# SensorBoardv2.net
KiCad netlist of a schematic drawn in Altium Designer
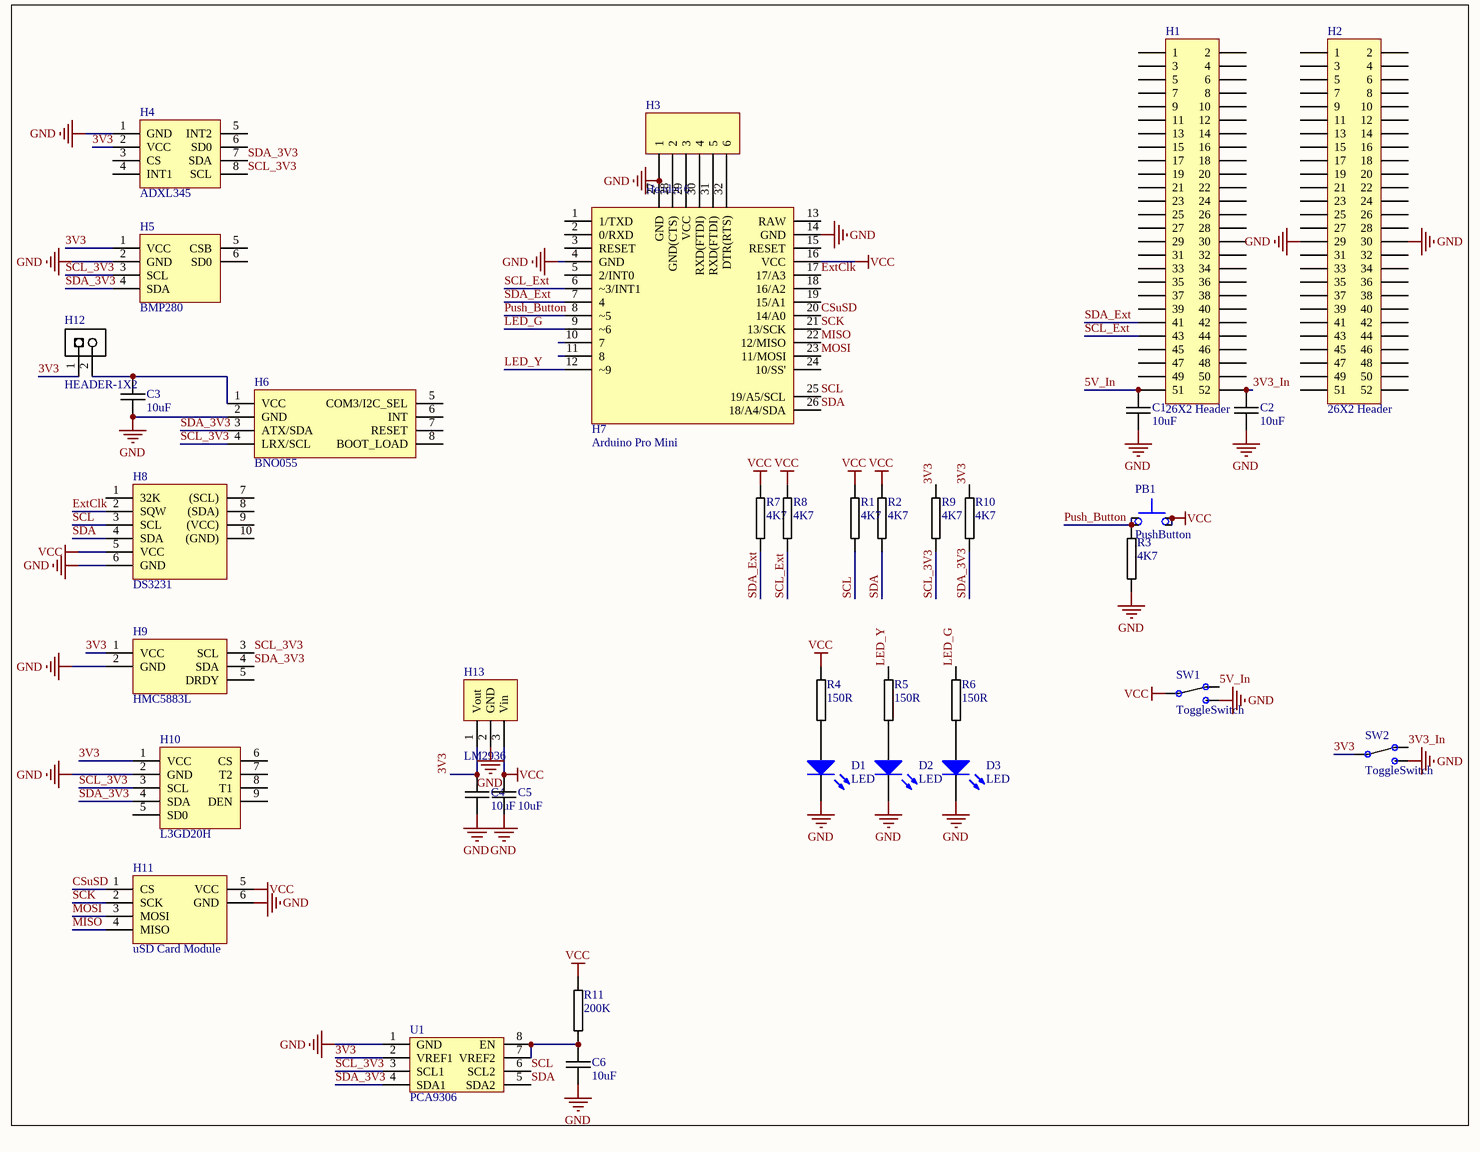
[diagram p0: SensorBoardv2.SchDoc]

(export (version "E")
  (design (tool "Eeschema 10.0.6"))
  (components
    (comp (ref "C1")
      (value "10uF")
      (footprint "0805C-TBD")
      (description "CAPACITOR 0805 CERAMIC")
      (libsource (lib "vh_altium_library") (part "0805C-100nF-25V-X7R-MUR"))
    )
    (comp (ref "C2")
      (value "10uF")
      (footprint "0805C-TBD")
      (description "CAPACITOR 0805 CERAMIC")
      (libsource (lib "vh_altium_library") (part "0805C-100nF-25V-X7R-MUR"))
    )
    (comp (ref "C3")
      (value "10uF")
      (footprint "0805C-GENERIC")
      (description "CAPACITOR 0805 CERAMIC")
      (fields
        (field (name "MANUFACTURER PART NUMBER") "C2012X5R1C106M")
        (field (name "MANUFACTURER") "TDK Corporation")
      )
      (libsource (lib "vh_altium_library") (part "0805C-10UF-16V-X5R-TDK"))
    )
    (comp (ref "C4")
      (value "10uF")
      (footprint "0805C-GENERIC")
      (description "CAPACITOR 0805 CERAMIC")
      (fields
        (field (name "MANUFACTURER PART NUMBER") "C2012X5R1C106M")
        (field (name "MANUFACTURER") "TDK Corporation")
      )
      (libsource (lib "vh_altium_library") (part "0805C-10UF-16V-X5R-TDK"))
    )
    (comp (ref "C5")
      (value "10uF")
      (footprint "0805C-GENERIC")
      (description "CAPACITOR 0805 CERAMIC")
      (fields
        (field (name "MANUFACTURER PART NUMBER") "C2012X5R1C106M")
        (field (name "MANUFACTURER") "TDK Corporation")
      )
      (libsource (lib "vh_altium_library") (part "0805C-10UF-16V-X5R-TDK"))
    )
    (comp (ref "C6")
      (value "10uF")
      (footprint "0805C-GENERIC")
      (description "CAPACITOR 0805 CERAMIC")
      (fields
        (field (name "MANUFACTURER PART NUMBER") "C2012X5R1C106M")
        (field (name "MANUFACTURER") "TDK Corporation")
      )
      (libsource (lib "vh_altium_library") (part "0805C-10UF-16V-X5R-TDK"))
    )
    (comp (ref "D1")
      (value "LED")
      (footprint "LED")
      (description "Small LED")
      (libsource (lib "Components") (part "LED"))
    )
    (comp (ref "D2")
      (value "LED")
      (footprint "LED")
      (description "Small LED")
      (libsource (lib "Components") (part "LED"))
    )
    (comp (ref "D3")
      (value "LED")
      (footprint "LED")
      (description "Small LED")
      (libsource (lib "Components") (part "LED"))
    )
    (comp (ref "H1")
      (value "26X2 Header")
      (footprint "26X2 Header")
      (libsource (lib "CustomParts") (part "26X2 Header"))
    )
    (comp (ref "H2")
      (value "26X2 Header")
      (footprint "26X2 Header")
      (libsource (lib "CustomParts") (part "26X2 Header"))
    )
    (comp (ref "H3")
      (value "Header 6")
      (footprint "HDR1X6")
      (description "Header, 6-Pin")
      (fields (field (name "PUBLISHER") "Altium Limited"))
      (libsource (lib "Miscellaneous Connectors") (part "Header 6"))
    )
    (comp (ref "H4")
      (value "ADXL345")
      (footprint "ADXL345")
      (description "Accelerometer")
      (libsource (lib "Components") (part "ADXL345"))
    )
    (comp (ref "H5")
      (value "BMP280")
      (footprint "BMP280")
      (description "Temp + Pa Sensor")
      (libsource (lib "Components") (part "BMP280"))
    )
    (comp (ref "H6")
      (value "BNO055")
      (footprint "BNO055")
      (description "Accel+Gyro+Mag")
      (libsource (lib "Components") (part "BNO055"))
    )
    (comp (ref "H7")
      (value "Arduino Pro Mini")
      (footprint "Arduino Pro Mini")
      (libsource (lib "Components") (part "Arduino Pro Mini"))
    )
    (comp (ref "H8")
      (value "DS3231")
      (footprint "RTC")
      (description "RTC")
      (libsource (lib "Components") (part "DS3231"))
    )
    (comp (ref "H9")
      (value "HMC5883L")
      (footprint "HMC5883L")
      (description "Magnetometer")
      (libsource (lib "Components") (part "HMC5883L"))
    )
    (comp (ref "H10")
      (value "L3GD20H")
      (footprint "L3GD20H")
      (description "Gyroscope")
      (libsource (lib "Components") (part "L3GD20H"))
    )
    (comp (ref "H11")
      (value "uSD Card Module")
      (footprint "uSD Card Module")
      (libsource (lib "Components") (part "uSD Card Module"))
    )
    (comp (ref "H12")
      (value "HEADER-1X2")
      (footprint "HEADER-1X2")
      (libsource (lib "vh_altium_library") (part "HEADER-1X2"))
    )
    (comp (ref "H13")
      (value "LM2936")
      (footprint "LM2936")
      (description "3V3 Voltage Regulator")
      (libsource (lib "Components") (part "LM2936"))
    )
    (comp (ref "PB1")
      (value "PushButton")
      (footprint "PushButton")
      (libsource (lib "SBv1Components") (part "PushButton"))
    )
    (comp (ref "R1")
      (value "4K7")
      (footprint "0805R-4K7")
      (description "RESISTOR 0805 1/4 WATT THIN FILM")
      (libsource (lib "vh_altium_library") (part "0805R-4K7"))
    )
    (comp (ref "R2")
      (value "4K7")
      (footprint "0805R-4K7")
      (description "RESISTOR 0805 1/4 WATT THIN FILM")
      (libsource (lib "vh_altium_library") (part "0805R-4K7"))
    )
    (comp (ref "R3")
      (value "4K7")
      (footprint "0805R-4K7")
      (description "RESISTOR 0805 1/4 WATT THIN FILM")
      (libsource (lib "vh_altium_library") (part "0805R-4K7"))
    )
    (comp (ref "R4")
      (value "150R")
      (footprint "0805R-150")
      (description "RESISTOR 0805 1/4 WATT THIN FILM")
      (libsource (lib "vh_altium_library") (part "0805R-150"))
    )
    (comp (ref "R5")
      (value "150R")
      (footprint "0805R-150")
      (description "RESISTOR 0805 1/4 WATT THIN FILM")
      (libsource (lib "vh_altium_library") (part "0805R-150"))
    )
    (comp (ref "R6")
      (value "150R")
      (footprint "0805R-150")
      (description "RESISTOR 0805 1/4 WATT THIN FILM")
      (libsource (lib "vh_altium_library") (part "0805R-150"))
    )
    (comp (ref "R7")
      (value "4K7")
      (footprint "0805R-4K7")
      (description "RESISTOR 0805 1/4 WATT THIN FILM")
      (libsource (lib "vh_altium_library") (part "0805R-4K7"))
    )
    (comp (ref "R8")
      (value "4K7")
      (footprint "0805R-4K7")
      (description "RESISTOR 0805 1/4 WATT THIN FILM")
      (libsource (lib "vh_altium_library") (part "0805R-4K7"))
    )
    (comp (ref "R9")
      (value "4K7")
      (footprint "0805R-4K7")
      (description "RESISTOR 0805 1/4 WATT THIN FILM")
      (libsource (lib "vh_altium_library") (part "0805R-4K7"))
    )
    (comp (ref "R10")
      (value "4K7")
      (footprint "0805R-4K7")
      (description "RESISTOR 0805 1/4 WATT THIN FILM")
      (libsource (lib "vh_altium_library") (part "0805R-4K7"))
    )
    (comp (ref "R11")
      (value "200K")
      (footprint "0805R-4K7")
      (description "RESISTOR 0805 1/4 WATT THIN FILM")
      (libsource (lib "vh_altium_library") (part "0805R-4K7"))
    )
    (comp (ref "SW1")
      (value "ToggleSwitch")
      (footprint "SWITCHFOOTPRINT")
      (libsource (lib "SBv1Components") (part "ToggleSwitch"))
    )
    (comp (ref "SW2")
      (value "ToggleSwitch")
      (footprint "SWITCHFOOTPRINT")
      (libsource (lib "SBv1Components") (part "ToggleSwitch"))
    )
    (comp (ref "U1")
      (value "PCA9306")
      (footprint "PCA9306")
      (description "Dual Bidirectional I2C Voltage Level Translator")
      (libsource (lib "Components") (part "PCA9306"))
    )
  )
  (nets
    (net (code "1") (name "/3V3") (class "Default")
      (node (ref "C4") (pin "2") (pintype "passive"))
      (node (ref "H10") (pin "1") (pinfunction "VCC_1") (pintype "passive"))
      (node (ref "H12") (pin "1") (pintype "passive"))
      (node (ref "H13") (pin "1") (pinfunction "Vout_1") (pintype "passive"))
      (node (ref "H4") (pin "2") (pinfunction "VCC_2") (pintype "passive"))
      (node (ref "H5") (pin "1") (pinfunction "VCC_1") (pintype "passive"))
      (node (ref "H9") (pin "1") (pinfunction "VCC_1") (pintype "passive"))
      (node (ref "R10") (pin "1") (pintype "passive"))
      (node (ref "R9") (pin "1") (pintype "passive"))
      (node (ref "SW2") (pin "23") (pinfunction "23_23") (pintype "passive"))
      (node (ref "U1") (pin "2") (pinfunction "VREF1_2") (pintype "passive"))
    )
    (net (code "2") (name "/3V3_In") (class "Default")
      (node (ref "C2") (pin "1") (pintype "passive"))
      (node (ref "H1") (pin "52") (pinfunction "52_52") (pintype "passive"))
      (node (ref "SW2") (pin "24") (pinfunction "24_24") (pintype "passive"))
    )
    (net (code "3") (name "/5V_In") (class "Default")
      (node (ref "C1") (pin "1") (pintype "passive"))
      (node (ref "H1") (pin "51") (pinfunction "51_51") (pintype "passive"))
      (node (ref "SW1") (pin "24") (pinfunction "24_24") (pintype "passive"))
    )
    (net (code "4") (name "/CSuSD") (class "Default")
      (node (ref "H11") (pin "1") (pinfunction "CS_1") (pintype "passive"))
      (node (ref "H7") (pin "20") (pinfunction "14/A0_20") (pintype "passive"))
    )
    (net (code "5") (name "/ExtClk") (class "Default")
      (node (ref "H7") (pin "17") (pinfunction "17/A3_17") (pintype "passive"))
      (node (ref "H8") (pin "2") (pinfunction "SQW_2") (pintype "passive"))
    )
    (net (code "6") (name "/LED_G") (class "Default")
      (node (ref "H7") (pin "9") (pinfunction "~6_9") (pintype "passive"))
      (node (ref "R6") (pin "1") (pintype "passive"))
    )
    (net (code "7") (name "/LED_Y") (class "Default")
      (node (ref "H7") (pin "12") (pinfunction "~9_12") (pintype "passive"))
      (node (ref "R5") (pin "1") (pintype "passive"))
    )
    (net (code "8") (name "/MISO") (class "Default")
      (node (ref "H11") (pin "4") (pinfunction "MISO_4") (pintype "passive"))
      (node (ref "H7") (pin "22") (pinfunction "12/MISO_22") (pintype "passive"))
    )
    (net (code "9") (name "/MOSI") (class "Default")
      (node (ref "H11") (pin "3") (pinfunction "MOSI_3") (pintype "passive"))
      (node (ref "H7") (pin "23") (pinfunction "11/MOSI_23") (pintype "passive"))
    )
    (net (code "10") (name "/Push_Button") (class "Default")
      (node (ref "H7") (pin "8") (pinfunction "~5_8") (pintype "passive"))
      (node (ref "PB1") (pin "26") (pinfunction "26_26") (pintype "passive"))
      (node (ref "PB1") (pin "28") (pinfunction "28_28") (pintype "passive"))
      (node (ref "R3") (pin "1") (pintype "passive"))
    )
    (net (code "11") (name "/SCK") (class "Default")
      (node (ref "H11") (pin "2") (pinfunction "SCK_2") (pintype "passive"))
      (node (ref "H7") (pin "21") (pinfunction "13/SCK_21") (pintype "passive"))
    )
    (net (code "12") (name "/SCL") (class "Default")
      (node (ref "H7") (pin "25") (pinfunction "19/A5/SCL_25") (pintype "passive"))
      (node (ref "H8") (pin "3") (pinfunction "SCL_3") (pintype "passive"))
      (node (ref "R1") (pin "2") (pintype "passive"))
      (node (ref "U1") (pin "6") (pinfunction "SCL2_6") (pintype "passive"))
    )
    (net (code "13") (name "/SCL_3V3") (class "Default")
      (node (ref "H10") (pin "3") (pinfunction "SCL_3") (pintype "passive"))
      (node (ref "H4") (pin "8") (pinfunction "SCL_8") (pintype "passive"))
      (node (ref "H5") (pin "3") (pinfunction "SCL_3") (pintype "passive"))
      (node (ref "H6") (pin "4") (pinfunction "LRX/SCL_4") (pintype "passive"))
      (node (ref "H9") (pin "3") (pinfunction "SCL_3") (pintype "passive"))
      (node (ref "R9") (pin "2") (pintype "passive"))
      (node (ref "U1") (pin "3") (pinfunction "SCL1_3") (pintype "passive"))
    )
    (net (code "14") (name "/SCL_Ext") (class "Default")
      (node (ref "H1") (pin "43") (pinfunction "43_43") (pintype "passive"))
      (node (ref "H7") (pin "6") (pinfunction "~3/INT1_6") (pintype "passive"))
      (node (ref "R8") (pin "2") (pintype "passive"))
    )
    (net (code "15") (name "/SDA") (class "Default")
      (node (ref "H7") (pin "26") (pinfunction "18/A4/SDA_26") (pintype "passive"))
      (node (ref "H8") (pin "4") (pinfunction "SDA_4") (pintype "passive"))
      (node (ref "R2") (pin "2") (pintype "passive"))
      (node (ref "U1") (pin "5") (pinfunction "SDA2_5") (pintype "passive"))
    )
    (net (code "16") (name "/SDA_3V3") (class "Default")
      (node (ref "H10") (pin "4") (pinfunction "SDA_4") (pintype "passive"))
      (node (ref "H4") (pin "7") (pinfunction "SDA_7") (pintype "passive"))
      (node (ref "H5") (pin "4") (pinfunction "SDA_4") (pintype "passive"))
      (node (ref "H6") (pin "3") (pinfunction "ATX/SDA_3") (pintype "passive"))
      (node (ref "H9") (pin "4") (pinfunction "SDA_4") (pintype "passive"))
      (node (ref "R10") (pin "2") (pintype "passive"))
      (node (ref "U1") (pin "4") (pinfunction "SDA1_4") (pintype "passive"))
    )
    (net (code "17") (name "/SDA_Ext") (class "Default")
      (node (ref "H1") (pin "41") (pinfunction "41_41") (pintype "passive"))
      (node (ref "H7") (pin "7") (pinfunction "4_7") (pintype "passive"))
      (node (ref "R7") (pin "2") (pintype "passive"))
    )
    (net (code "18") (name "GND") (class "Default")
      (node (ref "C1") (pin "2") (pintype "passive"))
      (node (ref "C2") (pin "2") (pintype "passive"))
      (node (ref "C3") (pin "2") (pintype "passive"))
      (node (ref "C4") (pin "1") (pintype "passive"))
      (node (ref "C5") (pin "1") (pintype "passive"))
      (node (ref "C6") (pin "2") (pintype "passive"))
      (node (ref "D1") (pin "2") (pinfunction "K_2") (pintype "passive"))
      (node (ref "D2") (pin "2") (pinfunction "K_2") (pintype "passive"))
      (node (ref "D3") (pin "2") (pinfunction "K_2") (pintype "passive"))
      (node (ref "H10") (pin "2") (pinfunction "GND_2") (pintype "passive"))
      (node (ref "H11") (pin "6") (pinfunction "GND_6") (pintype "passive"))
      (node (ref "H13") (pin "2") (pinfunction "GND_2") (pintype "passive"))
      (node (ref "H2") (pin "29") (pinfunction "29_29") (pintype "passive"))
      (node (ref "H2") (pin "30") (pinfunction "30_30") (pintype "passive"))
      (node (ref "H3") (pin "1") (pinfunction "1_1") (pintype "passive"))
      (node (ref "H4") (pin "1") (pinfunction "GND_1") (pintype "passive"))
      (node (ref "H5") (pin "2") (pinfunction "GND_2") (pintype "passive"))
      (node (ref "H6") (pin "2") (pinfunction "GND_2") (pintype "passive"))
      (node (ref "H7") (pin "14") (pinfunction "GND_14") (pintype "passive"))
      (node (ref "H7") (pin "27") (pinfunction "GND_27") (pintype "passive"))
      (node (ref "H7") (pin "4") (pinfunction "GND_4") (pintype "passive"))
      (node (ref "H8") (pin "6") (pinfunction "GND_6") (pintype "passive"))
      (node (ref "H9") (pin "2") (pinfunction "GND_2") (pintype "passive"))
      (node (ref "R3") (pin "2") (pintype "passive"))
      (node (ref "SW1") (pin "25") (pinfunction "25_25") (pintype "passive"))
      (node (ref "SW2") (pin "25") (pinfunction "25_25") (pintype "passive"))
      (node (ref "U1") (pin "1") (pinfunction "GND_1") (pintype "passive"))
    )
    (net (code "19") (name "Net-(D1-A)") (class "Default")
      (node (ref "D1") (pin "1") (pinfunction "A_1") (pintype "passive"))
      (node (ref "R4") (pin "2") (pintype "passive"))
    )
    (net (code "20") (name "Net-(D2-A)") (class "Default")
      (node (ref "D2") (pin "1") (pinfunction "A_1") (pintype "passive"))
      (node (ref "R5") (pin "2") (pintype "passive"))
    )
    (net (code "21") (name "Net-(D3-A)") (class "Default")
      (node (ref "D3") (pin "1") (pinfunction "A_1") (pintype "passive"))
      (node (ref "R6") (pin "2") (pintype "passive"))
    )
    (net (code "22") (name "Net-(H3-Pad3)") (class "Default")
      (node (ref "H3") (pin "3") (pinfunction "3_3") (pintype "passive"))
      (node (ref "H7") (pin "29") (pinfunction "VCC_29") (pintype "passive"))
    )
    (net (code "23") (name "Net-(H3-Pad4)") (class "Default")
      (node (ref "H3") (pin "4") (pinfunction "4_4") (pintype "passive"))
      (node (ref "H7") (pin "30") (pinfunction "RXD(FTDI)_30") (pintype "passive"))
    )
    (net (code "24") (name "Net-(H3-Pad5)") (class "Default")
      (node (ref "H3") (pin "5") (pinfunction "5_5") (pintype "passive"))
      (node (ref "H7") (pin "31") (pinfunction "RXD(FTDI)_31") (pintype "passive"))
    )
    (net (code "25") (name "Net-(H6-VCC)") (class "Default")
      (node (ref "C3") (pin "1") (pintype "passive"))
      (node (ref "H12") (pin "2") (pintype "passive"))
      (node (ref "H6") (pin "1") (pinfunction "VCC_1") (pintype "passive"))
    )
    (net (code "26") (name "Net-(H7-DTR(RTS))") (class "Default")
      (node (ref "H3") (pin "6") (pinfunction "6_6") (pintype "passive"))
      (node (ref "H7") (pin "32") (pinfunction "DTR(RTS)_32") (pintype "passive"))
    )
    (net (code "27") (name "Net-(H7-GND(CTS))") (class "Default")
      (node (ref "H3") (pin "2") (pinfunction "2_2") (pintype "passive"))
      (node (ref "H7") (pin "28") (pinfunction "GND(CTS)_28") (pintype "passive"))
    )
    (net (code "28") (name "Net-(U1-EN)") (class "Default")
      (node (ref "C6") (pin "1") (pintype "passive"))
      (node (ref "R11") (pin "1") (pintype "passive"))
      (node (ref "U1") (pin "7") (pinfunction "VREF2_7") (pintype "passive"))
      (node (ref "U1") (pin "8") (pinfunction "EN_8") (pintype "passive"))
    )
    (net (code "29") (name "VCC") (class "Default")
      (node (ref "C5") (pin "2") (pintype "passive"))
      (node (ref "H11") (pin "5") (pinfunction "VCC_5") (pintype "passive"))
      (node (ref "H13") (pin "3") (pinfunction "Vin_3") (pintype "passive"))
      (node (ref "H7") (pin "16") (pinfunction "VCC_16") (pintype "passive"))
      (node (ref "H8") (pin "5") (pinfunction "VCC_5") (pintype "passive"))
      (node (ref "PB1") (pin "27") (pinfunction "27_27") (pintype "passive"))
      (node (ref "PB1") (pin "29") (pinfunction "29_29") (pintype "passive"))
      (node (ref "R1") (pin "1") (pintype "passive"))
      (node (ref "R11") (pin "2") (pintype "passive"))
      (node (ref "R2") (pin "1") (pintype "passive"))
      (node (ref "R4") (pin "1") (pintype "passive"))
      (node (ref "R7") (pin "1") (pintype "passive"))
      (node (ref "R8") (pin "1") (pintype "passive"))
      (node (ref "SW1") (pin "23") (pinfunction "23_23") (pintype "passive"))
    )
    (net (code "30") (name "unconnected-(H1-Pad1)") (class "Default")
      (node (ref "H1") (pin "1") (pinfunction "1_1") (pintype "passive"))
    )
    (net (code "31") (name "unconnected-(H1-Pad2)") (class "Default")
      (node (ref "H1") (pin "2") (pinfunction "2_2") (pintype "passive"))
    )
    (net (code "32") (name "unconnected-(H1-Pad3)") (class "Default")
      (node (ref "H1") (pin "3") (pinfunction "3_3") (pintype "passive"))
    )
    (net (code "33") (name "unconnected-(H1-Pad4)") (class "Default")
      (node (ref "H1") (pin "4") (pinfunction "4_4") (pintype "passive"))
    )
    (net (code "34") (name "unconnected-(H1-Pad5)") (class "Default")
      (node (ref "H1") (pin "5") (pinfunction "5_5") (pintype "passive"))
    )
    (net (code "35") (name "unconnected-(H1-Pad6)") (class "Default")
      (node (ref "H1") (pin "6") (pinfunction "6_6") (pintype "passive"))
    )
    (net (code "36") (name "unconnected-(H1-Pad7)") (class "Default")
      (node (ref "H1") (pin "7") (pinfunction "7_7") (pintype "passive"))
    )
    (net (code "37") (name "unconnected-(H1-Pad8)") (class "Default")
      (node (ref "H1") (pin "8") (pinfunction "8_8") (pintype "passive"))
    )
    (net (code "38") (name "unconnected-(H1-Pad9)") (class "Default")
      (node (ref "H1") (pin "9") (pinfunction "9_9") (pintype "passive"))
    )
    (net (code "39") (name "unconnected-(H1-Pad10)") (class "Default")
      (node (ref "H1") (pin "10") (pinfunction "10_10") (pintype "passive"))
    )
    (net (code "40") (name "unconnected-(H1-Pad11)") (class "Default")
      (node (ref "H1") (pin "11") (pinfunction "11_11") (pintype "passive"))
    )
    (net (code "41") (name "unconnected-(H1-Pad12)") (class "Default")
      (node (ref "H1") (pin "12") (pinfunction "12_12") (pintype "passive"))
    )
    (net (code "42") (name "unconnected-(H1-Pad13)") (class "Default")
      (node (ref "H1") (pin "13") (pinfunction "13_13") (pintype "passive"))
    )
    (net (code "43") (name "unconnected-(H1-Pad14)") (class "Default")
      (node (ref "H1") (pin "14") (pinfunction "14_14") (pintype "passive"))
    )
    (net (code "44") (name "unconnected-(H1-Pad15)") (class "Default")
      (node (ref "H1") (pin "15") (pinfunction "15_15") (pintype "passive"))
    )
    (net (code "45") (name "unconnected-(H1-Pad16)") (class "Default")
      (node (ref "H1") (pin "16") (pinfunction "16_16") (pintype "passive"))
    )
    (net (code "46") (name "unconnected-(H1-Pad17)") (class "Default")
      (node (ref "H1") (pin "17") (pinfunction "17_17") (pintype "passive"))
    )
    (net (code "47") (name "unconnected-(H1-Pad18)") (class "Default")
      (node (ref "H1") (pin "18") (pinfunction "18_18") (pintype "passive"))
    )
    (net (code "48") (name "unconnected-(H1-Pad19)") (class "Default")
      (node (ref "H1") (pin "19") (pinfunction "19_19") (pintype "passive"))
    )
    (net (code "49") (name "unconnected-(H1-Pad20)") (class "Default")
      (node (ref "H1") (pin "20") (pinfunction "20_20") (pintype "passive"))
    )
    (net (code "50") (name "unconnected-(H1-Pad21)") (class "Default")
      (node (ref "H1") (pin "21") (pinfunction "21_21") (pintype "passive"))
    )
    (net (code "51") (name "unconnected-(H1-Pad22)") (class "Default")
      (node (ref "H1") (pin "22") (pinfunction "22_22") (pintype "passive"))
    )
    (net (code "52") (name "unconnected-(H1-Pad23)") (class "Default")
      (node (ref "H1") (pin "23") (pinfunction "23_23") (pintype "passive"))
    )
    (net (code "53") (name "unconnected-(H1-Pad24)") (class "Default")
      (node (ref "H1") (pin "24") (pinfunction "24_24") (pintype "passive"))
    )
    (net (code "54") (name "unconnected-(H1-Pad25)") (class "Default")
      (node (ref "H1") (pin "25") (pinfunction "25_25") (pintype "passive"))
    )
    (net (code "55") (name "unconnected-(H1-Pad26)") (class "Default")
      (node (ref "H1") (pin "26") (pinfunction "26_26") (pintype "passive"))
    )
    (net (code "56") (name "unconnected-(H1-Pad27)") (class "Default")
      (node (ref "H1") (pin "27") (pinfunction "27_27") (pintype "passive"))
    )
    (net (code "57") (name "unconnected-(H1-Pad28)") (class "Default")
      (node (ref "H1") (pin "28") (pinfunction "28_28") (pintype "passive"))
    )
    (net (code "58") (name "unconnected-(H1-Pad29)") (class "Default")
      (node (ref "H1") (pin "29") (pinfunction "29_29") (pintype "passive"))
    )
    (net (code "59") (name "unconnected-(H1-Pad30)") (class "Default")
      (node (ref "H1") (pin "30") (pinfunction "30_30") (pintype "passive"))
    )
    (net (code "60") (name "unconnected-(H1-Pad31)") (class "Default")
      (node (ref "H1") (pin "31") (pinfunction "31_31") (pintype "passive"))
    )
    (net (code "61") (name "unconnected-(H1-Pad32)") (class "Default")
      (node (ref "H1") (pin "32") (pinfunction "32_32") (pintype "passive"))
    )
    (net (code "62") (name "unconnected-(H1-Pad33)") (class "Default")
      (node (ref "H1") (pin "33") (pinfunction "33_33") (pintype "passive"))
    )
    (net (code "63") (name "unconnected-(H1-Pad34)") (class "Default")
      (node (ref "H1") (pin "34") (pinfunction "34_34") (pintype "passive"))
    )
    (net (code "64") (name "unconnected-(H1-Pad35)") (class "Default")
      (node (ref "H1") (pin "35") (pinfunction "35_35") (pintype "passive"))
    )
    (net (code "65") (name "unconnected-(H1-Pad36)") (class "Default")
      (node (ref "H1") (pin "36") (pinfunction "36_36") (pintype "passive"))
    )
    (net (code "66") (name "unconnected-(H1-Pad37)") (class "Default")
      (node (ref "H1") (pin "37") (pinfunction "37_37") (pintype "passive"))
    )
    (net (code "67") (name "unconnected-(H1-Pad38)") (class "Default")
      (node (ref "H1") (pin "38") (pinfunction "38_38") (pintype "passive"))
    )
    (net (code "68") (name "unconnected-(H1-Pad39)") (class "Default")
      (node (ref "H1") (pin "39") (pinfunction "39_39") (pintype "passive"))
    )
    (net (code "69") (name "unconnected-(H1-Pad40)") (class "Default")
      (node (ref "H1") (pin "40") (pinfunction "40_40") (pintype "passive"))
    )
    (net (code "70") (name "unconnected-(H1-Pad42)") (class "Default")
      (node (ref "H1") (pin "42") (pinfunction "42_42") (pintype "passive"))
    )
    (net (code "71") (name "unconnected-(H1-Pad44)") (class "Default")
      (node (ref "H1") (pin "44") (pinfunction "44_44") (pintype "passive"))
    )
    (net (code "72") (name "unconnected-(H1-Pad45)") (class "Default")
      (node (ref "H1") (pin "45") (pinfunction "45_45") (pintype "passive"))
    )
    (net (code "73") (name "unconnected-(H1-Pad46)") (class "Default")
      (node (ref "H1") (pin "46") (pinfunction "46_46") (pintype "passive"))
    )
    (net (code "74") (name "unconnected-(H1-Pad47)") (class "Default")
      (node (ref "H1") (pin "47") (pinfunction "47_47") (pintype "passive"))
    )
    (net (code "75") (name "unconnected-(H1-Pad48)") (class "Default")
      (node (ref "H1") (pin "48") (pinfunction "48_48") (pintype "passive"))
    )
    (net (code "76") (name "unconnected-(H1-Pad49)") (class "Default")
      (node (ref "H1") (pin "49") (pinfunction "49_49") (pintype "passive"))
    )
    (net (code "77") (name "unconnected-(H1-Pad50)") (class "Default")
      (node (ref "H1") (pin "50") (pinfunction "50_50") (pintype "passive"))
    )
    (net (code "78") (name "unconnected-(H2-Pad1)") (class "Default")
      (node (ref "H2") (pin "1") (pinfunction "1_1") (pintype "passive"))
    )
    (net (code "79") (name "unconnected-(H2-Pad2)") (class "Default")
      (node (ref "H2") (pin "2") (pinfunction "2_2") (pintype "passive"))
    )
    (net (code "80") (name "unconnected-(H2-Pad3)") (class "Default")
      (node (ref "H2") (pin "3") (pinfunction "3_3") (pintype "passive"))
    )
    (net (code "81") (name "unconnected-(H2-Pad4)") (class "Default")
      (node (ref "H2") (pin "4") (pinfunction "4_4") (pintype "passive"))
    )
    (net (code "82") (name "unconnected-(H2-Pad5)") (class "Default")
      (node (ref "H2") (pin "5") (pinfunction "5_5") (pintype "passive"))
    )
    (net (code "83") (name "unconnected-(H2-Pad6)") (class "Default")
      (node (ref "H2") (pin "6") (pinfunction "6_6") (pintype "passive"))
    )
    (net (code "84") (name "unconnected-(H2-Pad7)") (class "Default")
      (node (ref "H2") (pin "7") (pinfunction "7_7") (pintype "passive"))
    )
    (net (code "85") (name "unconnected-(H2-Pad8)") (class "Default")
      (node (ref "H2") (pin "8") (pinfunction "8_8") (pintype "passive"))
    )
    (net (code "86") (name "unconnected-(H2-Pad9)") (class "Default")
      (node (ref "H2") (pin "9") (pinfunction "9_9") (pintype "passive"))
    )
    (net (code "87") (name "unconnected-(H2-Pad10)") (class "Default")
      (node (ref "H2") (pin "10") (pinfunction "10_10") (pintype "passive"))
    )
    (net (code "88") (name "unconnected-(H2-Pad11)") (class "Default")
      (node (ref "H2") (pin "11") (pinfunction "11_11") (pintype "passive"))
    )
    (net (code "89") (name "unconnected-(H2-Pad12)") (class "Default")
      (node (ref "H2") (pin "12") (pinfunction "12_12") (pintype "passive"))
    )
    (net (code "90") (name "unconnected-(H2-Pad13)") (class "Default")
      (node (ref "H2") (pin "13") (pinfunction "13_13") (pintype "passive"))
    )
    (net (code "91") (name "unconnected-(H2-Pad14)") (class "Default")
      (node (ref "H2") (pin "14") (pinfunction "14_14") (pintype "passive"))
    )
    (net (code "92") (name "unconnected-(H2-Pad15)") (class "Default")
      (node (ref "H2") (pin "15") (pinfunction "15_15") (pintype "passive"))
    )
    (net (code "93") (name "unconnected-(H2-Pad16)") (class "Default")
      (node (ref "H2") (pin "16") (pinfunction "16_16") (pintype "passive"))
    )
    (net (code "94") (name "unconnected-(H2-Pad17)") (class "Default")
      (node (ref "H2") (pin "17") (pinfunction "17_17") (pintype "passive"))
    )
    (net (code "95") (name "unconnected-(H2-Pad18)") (class "Default")
      (node (ref "H2") (pin "18") (pinfunction "18_18") (pintype "passive"))
    )
    (net (code "96") (name "unconnected-(H2-Pad19)") (class "Default")
      (node (ref "H2") (pin "19") (pinfunction "19_19") (pintype "passive"))
    )
    (net (code "97") (name "unconnected-(H2-Pad20)") (class "Default")
      (node (ref "H2") (pin "20") (pinfunction "20_20") (pintype "passive"))
    )
    (net (code "98") (name "unconnected-(H2-Pad21)") (class "Default")
      (node (ref "H2") (pin "21") (pinfunction "21_21") (pintype "passive"))
    )
    (net (code "99") (name "unconnected-(H2-Pad22)") (class "Default")
      (node (ref "H2") (pin "22") (pinfunction "22_22") (pintype "passive"))
    )
    (net (code "100") (name "unconnected-(H2-Pad23)") (class "Default")
      (node (ref "H2") (pin "23") (pinfunction "23_23") (pintype "passive"))
    )
    (net (code "101") (name "unconnected-(H2-Pad24)") (class "Default")
      (node (ref "H2") (pin "24") (pinfunction "24_24") (pintype "passive"))
    )
    (net (code "102") (name "unconnected-(H2-Pad25)") (class "Default")
      (node (ref "H2") (pin "25") (pinfunction "25_25") (pintype "passive"))
    )
    (net (code "103") (name "unconnected-(H2-Pad26)") (class "Default")
      (node (ref "H2") (pin "26") (pinfunction "26_26") (pintype "passive"))
    )
    (net (code "104") (name "unconnected-(H2-Pad27)") (class "Default")
      (node (ref "H2") (pin "27") (pinfunction "27_27") (pintype "passive"))
    )
    (net (code "105") (name "unconnected-(H2-Pad28)") (class "Default")
      (node (ref "H2") (pin "28") (pinfunction "28_28") (pintype "passive"))
    )
    (net (code "106") (name "unconnected-(H2-Pad31)") (class "Default")
      (node (ref "H2") (pin "31") (pinfunction "31_31") (pintype "passive"))
    )
    (net (code "107") (name "unconnected-(H2-Pad32)") (class "Default")
      (node (ref "H2") (pin "32") (pinfunction "32_32") (pintype "passive"))
    )
    (net (code "108") (name "unconnected-(H2-Pad33)") (class "Default")
      (node (ref "H2") (pin "33") (pinfunction "33_33") (pintype "passive"))
    )
    (net (code "109") (name "unconnected-(H2-Pad34)") (class "Default")
      (node (ref "H2") (pin "34") (pinfunction "34_34") (pintype "passive"))
    )
    (net (code "110") (name "unconnected-(H2-Pad35)") (class "Default")
      (node (ref "H2") (pin "35") (pinfunction "35_35") (pintype "passive"))
    )
    (net (code "111") (name "unconnected-(H2-Pad36)") (class "Default")
      (node (ref "H2") (pin "36") (pinfunction "36_36") (pintype "passive"))
    )
    (net (code "112") (name "unconnected-(H2-Pad37)") (class "Default")
      (node (ref "H2") (pin "37") (pinfunction "37_37") (pintype "passive"))
    )
    (net (code "113") (name "unconnected-(H2-Pad38)") (class "Default")
      (node (ref "H2") (pin "38") (pinfunction "38_38") (pintype "passive"))
    )
    (net (code "114") (name "unconnected-(H2-Pad39)") (class "Default")
      (node (ref "H2") (pin "39") (pinfunction "39_39") (pintype "passive"))
    )
    (net (code "115") (name "unconnected-(H2-Pad40)") (class "Default")
      (node (ref "H2") (pin "40") (pinfunction "40_40") (pintype "passive"))
    )
    (net (code "116") (name "unconnected-(H2-Pad41)") (class "Default")
      (node (ref "H2") (pin "41") (pinfunction "41_41") (pintype "passive"))
    )
    (net (code "117") (name "unconnected-(H2-Pad42)") (class "Default")
      (node (ref "H2") (pin "42") (pinfunction "42_42") (pintype "passive"))
    )
    (net (code "118") (name "unconnected-(H2-Pad43)") (class "Default")
      (node (ref "H2") (pin "43") (pinfunction "43_43") (pintype "passive"))
    )
    (net (code "119") (name "unconnected-(H2-Pad44)") (class "Default")
      (node (ref "H2") (pin "44") (pinfunction "44_44") (pintype "passive"))
    )
    (net (code "120") (name "unconnected-(H2-Pad45)") (class "Default")
      (node (ref "H2") (pin "45") (pinfunction "45_45") (pintype "passive"))
    )
    (net (code "121") (name "unconnected-(H2-Pad46)") (class "Default")
      (node (ref "H2") (pin "46") (pinfunction "46_46") (pintype "passive"))
    )
    (net (code "122") (name "unconnected-(H2-Pad47)") (class "Default")
      (node (ref "H2") (pin "47") (pinfunction "47_47") (pintype "passive"))
    )
    (net (code "123") (name "unconnected-(H2-Pad48)") (class "Default")
      (node (ref "H2") (pin "48") (pinfunction "48_48") (pintype "passive"))
    )
    (net (code "124") (name "unconnected-(H2-Pad49)") (class "Default")
      (node (ref "H2") (pin "49") (pinfunction "49_49") (pintype "passive"))
    )
    (net (code "125") (name "unconnected-(H2-Pad50)") (class "Default")
      (node (ref "H2") (pin "50") (pinfunction "50_50") (pintype "passive"))
    )
    (net (code "126") (name "unconnected-(H2-Pad51)") (class "Default")
      (node (ref "H2") (pin "51") (pinfunction "51_51") (pintype "passive"))
    )
    (net (code "127") (name "unconnected-(H2-Pad52)") (class "Default")
      (node (ref "H2") (pin "52") (pinfunction "52_52") (pintype "passive"))
    )
    (net (code "128") (name "unconnected-(H4-CS-Pad3)") (class "Default")
      (node (ref "H4") (pin "3") (pinfunction "CS_3") (pintype "passive"))
    )
    (net (code "129") (name "unconnected-(H4-INT1-Pad4)") (class "Default")
      (node (ref "H4") (pin "4") (pinfunction "INT1_4") (pintype "passive"))
    )
    (net (code "130") (name "unconnected-(H4-INT2-Pad5)") (class "Default")
      (node (ref "H4") (pin "5") (pinfunction "INT2_5") (pintype "passive"))
    )
    (net (code "131") (name "unconnected-(H4-SD0-Pad6)") (class "Default")
      (node (ref "H4") (pin "6") (pinfunction "SD0_6") (pintype "passive"))
    )
    (net (code "132") (name "unconnected-(H5-CSB-Pad5)") (class "Default")
      (node (ref "H5") (pin "5") (pinfunction "CSB_5") (pintype "passive"))
    )
    (net (code "133") (name "unconnected-(H5-SD0-Pad6)") (class "Default")
      (node (ref "H5") (pin "6") (pinfunction "SD0_6") (pintype "passive"))
    )
    (net (code "134") (name "unconnected-(H6-BOOT_LOAD-Pad8)") (class "Default")
      (node (ref "H6") (pin "8") (pinfunction "BOOT_LOAD_8") (pintype "passive"))
    )
    (net (code "135") (name "unconnected-(H6-COM3{slash}I2C_SEL-Pad5)") (class "Default")
      (node (ref "H6") (pin "5") (pinfunction "COM3/I2C_SEL_5") (pintype "passive"))
    )
    (net (code "136") (name "unconnected-(H6-INT-Pad6)") (class "Default")
      (node (ref "H6") (pin "6") (pinfunction "INT_6") (pintype "passive"))
    )
    (net (code "137") (name "unconnected-(H6-RESET-Pad7)") (class "Default")
      (node (ref "H6") (pin "7") (pinfunction "RESET_7") (pintype "passive"))
    )
    (net (code "138") (name "unconnected-(H7-0{slash}RXD-Pad2)") (class "Default")
      (node (ref "H7") (pin "2") (pinfunction "0/RXD_2") (pintype "passive"))
    )
    (net (code "139") (name "unconnected-(H7-1{slash}TXD-Pad1)") (class "Default")
      (node (ref "H7") (pin "1") (pinfunction "1/TXD_1") (pintype "passive"))
    )
    (net (code "140") (name "unconnected-(H7-2{slash}INT0-Pad5)") (class "Default")
      (node (ref "H7") (pin "5") (pinfunction "2/INT0_5") (pintype "passive"))
    )
    (net (code "141") (name "unconnected-(H7-7-Pad10)") (class "Default")
      (node (ref "H7") (pin "10") (pinfunction "7_10") (pintype "passive"))
    )
    (net (code "142") (name "unconnected-(H7-8-Pad11)") (class "Default")
      (node (ref "H7") (pin "11") (pinfunction "8_11") (pintype "passive"))
    )
    (net (code "143") (name "unconnected-(H7-10{slash}SS'-Pad24)") (class "Default")
      (node (ref "H7") (pin "24") (pinfunction "10/SS'_24") (pintype "passive"))
    )
    (net (code "144") (name "unconnected-(H7-15{slash}A1-Pad19)") (class "Default")
      (node (ref "H7") (pin "19") (pinfunction "15/A1_19") (pintype "passive"))
    )
    (net (code "145") (name "unconnected-(H7-16{slash}A2-Pad18)") (class "Default")
      (node (ref "H7") (pin "18") (pinfunction "16/A2_18") (pintype "passive"))
    )
    (net (code "146") (name "unconnected-(H7-RAW-Pad13)") (class "Default")
      (node (ref "H7") (pin "13") (pinfunction "RAW_13") (pintype "passive"))
    )
    (net (code "147") (name "unconnected-(H7-RESET-Pad3)") (class "Default")
      (node (ref "H7") (pin "3") (pinfunction "RESET_3") (pintype "passive"))
    )
    (net (code "148") (name "unconnected-(H7-RESET-Pad15)") (class "Default")
      (node (ref "H7") (pin "15") (pinfunction "RESET_15") (pintype "passive"))
    )
    (net (code "149") (name "unconnected-(H8-(GND)-Pad10)") (class "Default")
      (node (ref "H8") (pin "10") (pinfunction "(GND)_10") (pintype "passive"))
    )
    (net (code "150") (name "unconnected-(H8-(SCL)-Pad7)") (class "Default")
      (node (ref "H8") (pin "7") (pinfunction "(SCL)_7") (pintype "passive"))
    )
    (net (code "151") (name "unconnected-(H8-(SDA)-Pad8)") (class "Default")
      (node (ref "H8") (pin "8") (pinfunction "(SDA)_8") (pintype "passive"))
    )
    (net (code "152") (name "unconnected-(H8-(VCC)-Pad9)") (class "Default")
      (node (ref "H8") (pin "9") (pinfunction "(VCC)_9") (pintype "passive"))
    )
    (net (code "153") (name "unconnected-(H8-32K-Pad1)") (class "Default")
      (node (ref "H8") (pin "1") (pinfunction "32K_1") (pintype "passive"))
    )
    (net (code "154") (name "unconnected-(H9-DRDY-Pad5)") (class "Default")
      (node (ref "H9") (pin "5") (pinfunction "DRDY_5") (pintype "passive"))
    )
    (net (code "155") (name "unconnected-(H10-CS-Pad6)") (class "Default")
      (node (ref "H10") (pin "6") (pinfunction "CS_6") (pintype "passive"))
    )
    (net (code "156") (name "unconnected-(H10-DEN-Pad9)") (class "Default")
      (node (ref "H10") (pin "9") (pinfunction "DEN_9") (pintype "passive"))
    )
    (net (code "157") (name "unconnected-(H10-SD0-Pad5)") (class "Default")
      (node (ref "H10") (pin "5") (pinfunction "SD0_5") (pintype "passive"))
    )
    (net (code "158") (name "unconnected-(H10-T1-Pad8)") (class "Default")
      (node (ref "H10") (pin "8") (pinfunction "T1_8") (pintype "passive"))
    )
    (net (code "159") (name "unconnected-(H10-T2-Pad7)") (class "Default")
      (node (ref "H10") (pin "7") (pinfunction "T2_7") (pintype "passive"))
    )
  )
)
